# ESP-12.net
KiCad netlist of a schematic drawn in Altium Designer
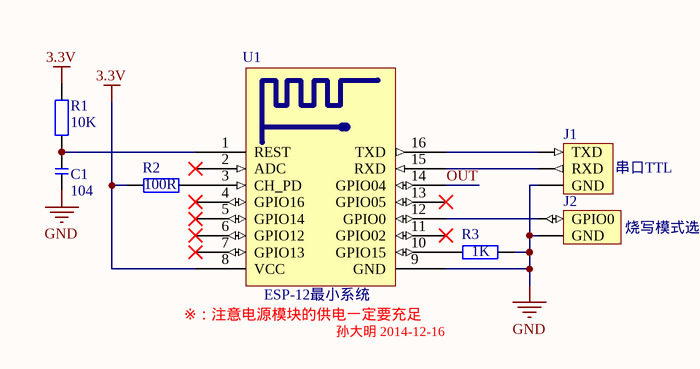
[diagram p0: ESP-12.SchDoc]

(export (version "E")
  (design (tool "Eeschema 10.0.6"))
  (components
    (comp (ref "C1") (value "104") (footprint "0805") (libsource (lib "ESP-12") (part "无极性电容 0805")))
    (comp (ref "J1") (value "USART") (libsource (lib "ESP-12") (part "USART")))
    (comp (ref "J2") (value "GPIO0") (libsource (lib "ESP-12") (part "GPIO0")))
    (comp (ref "R1") (value "10K") (footprint "0805") (libsource (lib "ESP-12") (part "电阻 0805")))
    (comp (ref "R2") (value "100R") (footprint "0805") (libsource (lib "ESP-12") (part "电阻 0805")))
    (comp (ref "R3") (value "1K") (footprint "0805") (libsource (lib "ESP-12") (part "电阻 0805")))
    (comp (ref "U1") (value "ESP-12") (libsource (lib "ESP-12") (part "ESP-12")))
  )
  (nets
    (net (code "1") (name "/OUT") (class "Default")
      (node (ref "U1") (pin "14") (pinfunction "GPIO04_14") (pintype "bidirectional"))
    )
    (net (code "2") (name "3.3V") (class "Default")
      (node (ref "R1") (pin "2") (pinfunction "1_2") (pintype "passive"))
      (node (ref "R2") (pin "1") (pinfunction "0_1") (pintype "passive"))
      (node (ref "U1") (pin "8") (pinfunction "VCC_8") (pintype "power_in"))
    )
    (net (code "3") (name "GND") (class "Default")
      (node (ref "C1") (pin "1") (pinfunction "0_1") (pintype "passive"))
      (node (ref "J1") (pin "3") (pinfunction "GND_3") (pintype "passive"))
      (node (ref "J2") (pin "2") (pinfunction "GND_2") (pintype "power_in"))
      (node (ref "R3") (pin "2") (pinfunction "1_2") (pintype "passive"))
      (node (ref "U1") (pin "9") (pinfunction "GND_9") (pintype "power_in"))
    )
    (net (code "4") (name "Net-(C1-1)") (class "Default")
      (node (ref "C1") (pin "2") (pinfunction "1_2") (pintype "passive"))
      (node (ref "R1") (pin "1") (pinfunction "0_1") (pintype "passive"))
      (node (ref "U1") (pin "1") (pinfunction "REST_1") (pintype "passive"))
    )
    (net (code "5") (name "Net-(J1-RXD)") (class "Default")
      (node (ref "J1") (pin "2") (pinfunction "RXD_2") (pintype "output"))
      (node (ref "U1") (pin "15") (pinfunction "RXD_15") (pintype "input"))
    )
    (net (code "6") (name "Net-(J1-TXD)") (class "Default")
      (node (ref "J1") (pin "1") (pinfunction "TXD_1") (pintype "input"))
      (node (ref "U1") (pin "16") (pinfunction "TXD_16") (pintype "output"))
    )
    (net (code "7") (name "Net-(J2-GPIO0)") (class "Default")
      (node (ref "J2") (pin "1") (pinfunction "GPIO0_1") (pintype "bidirectional"))
      (node (ref "U1") (pin "12") (pinfunction "GPIO0_12") (pintype "bidirectional"))
    )
    (net (code "8") (name "Net-(R2-1)") (class "Default")
      (node (ref "R2") (pin "2") (pinfunction "1_2") (pintype "passive"))
      (node (ref "U1") (pin "3") (pinfunction "CH_PD_3") (pintype "input"))
    )
    (net (code "9") (name "Net-(R3-0)") (class "Default")
      (node (ref "R3") (pin "1") (pinfunction "0_1") (pintype "passive"))
      (node (ref "U1") (pin "10") (pinfunction "GPIO15_10") (pintype "bidirectional"))
    )
    (net (code "10") (name "unconnected-(U1-ADC-Pad2)") (class "Default")
      (node (ref "U1") (pin "2") (pinfunction "ADC_2") (pintype "input+no_connect"))
    )
    (net (code "11") (name "unconnected-(U1-GPIO02-Pad11)") (class "Default")
      (node (ref "U1") (pin "11") (pinfunction "GPIO02_11") (pintype "bidirectional+no_connect"))
    )
    (net (code "12") (name "unconnected-(U1-GPIO05-Pad13)") (class "Default")
      (node (ref "U1") (pin "13") (pinfunction "GPIO05_13") (pintype "bidirectional+no_connect"))
    )
    (net (code "13") (name "unconnected-(U1-GPIO12-Pad6)") (class "Default")
      (node (ref "U1") (pin "6") (pinfunction "GPIO12_6") (pintype "bidirectional+no_connect"))
    )
    (net (code "14") (name "unconnected-(U1-GPIO13-Pad7)") (class "Default")
      (node (ref "U1") (pin "7") (pinfunction "GPIO13_7") (pintype "bidirectional+no_connect"))
    )
    (net (code "15") (name "unconnected-(U1-GPIO14-Pad5)") (class "Default")
      (node (ref "U1") (pin "5") (pinfunction "GPIO14_5") (pintype "bidirectional+no_connect"))
    )
    (net (code "16") (name "unconnected-(U1-GPIO16-Pad4)") (class "Default")
      (node (ref "U1") (pin "4") (pinfunction "GPIO16_4") (pintype "bidirectional+no_connect"))
    )
  )
)
